# 06_IN_OUT.net
KiCad netlist of a schematic drawn in Altium Designer
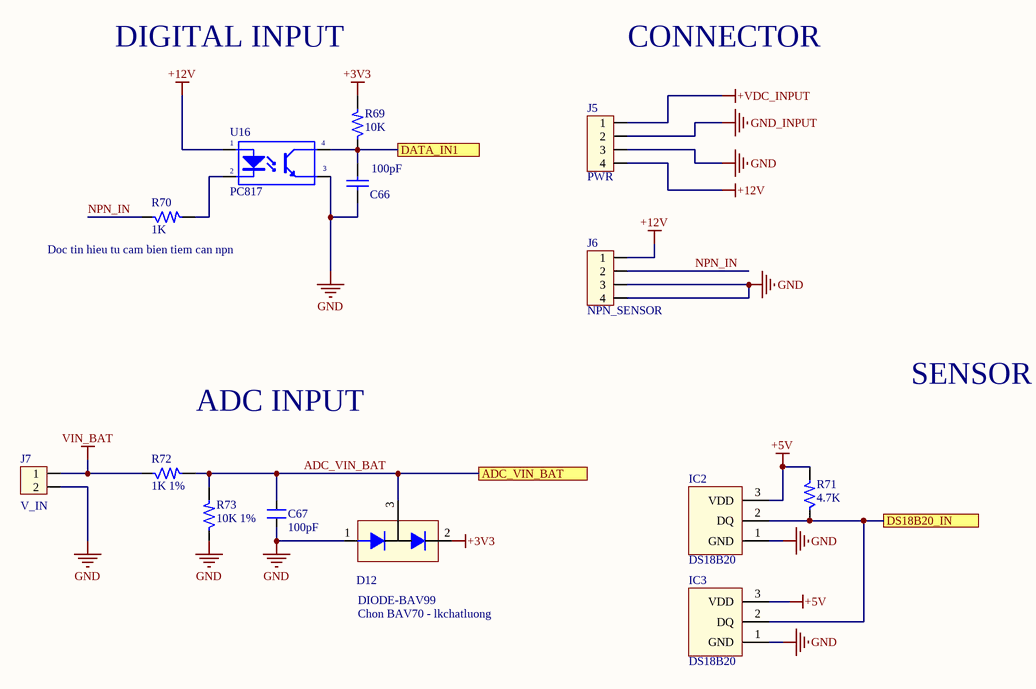
[diagram p0: [06]IN_OUT.SchDoc]

(export (version "E")
  (design (tool "Eeschema 10.0.6"))
  (components
    (comp (ref "C66")
      (value "100pF")
      (footprint "CAP_0805")
      (description "Capacitor")
      (fields (field (name "PUBLISHER") "Altium Limited"))
      (libsource (lib "My Library") (part "CapSMD"))
    )
    (comp (ref "C67")
      (value "100pF")
      (footprint "CAP_0805")
      (description "Cap SMD")
      (libsource (lib "khapham") (part "CM"))
    )
    (comp (ref "D12")
      (value "DIODE-BAV99")
      (footprint "SOT23")
      (description "ZENER, SOT23,")
      (fields
        (field (name "MANUFACTURER") "ON Semiconductor / Fairchild")
        (field (name "MANUFACTURER PART NUMBER") "BAV99")
        (field (name ".CREATOR") "LeKhaLinh")
        (field (name ".CHECKPCB") "LeKhaLinh")
        (field (name ".CHECKSCH") "LeKhaLinh")
      )
      (libsource (lib "GPS_Traking_V1_1") (part "DIODE-BAV99"))
    )
    (comp (ref "IC2")
      (value "DS18B20")
      (footprint "TO92")
      (description "High Precision  1-Wire® Digital Thermometer")
      (libsource (lib "My Library") (part "DS18S20"))
    )
    (comp (ref "IC3")
      (value "DS18B20")
      (footprint "TO92")
      (description "High Precision  1-Wire® Digital Thermometer")
      (libsource (lib "My Library") (part "DS18S20"))
    )
    (comp (ref "J5")
      (value "PWR")
      (footprint "Hed4V_3.96")
      (description "Header 4 (Green)")
      (libsource (lib "GPS_Traking_V1_1") (part "Hed4"))
    )
    (comp (ref "J6")
      (value "NPN_SENSOR")
      (footprint "CON_2.54mm_4")
      (description "Connector 4")
      (libsource (lib "GPS_Traking_V1_1") (part "Con4"))
    )
    (comp (ref "J7")
      (value "V_IN")
      (footprint "CON_2.54mm_2")
      (description "Connector 2")
      (libsource (lib "GPS_Traking_V1_1") (part "Con2"))
    )
    (comp (ref "R69")
      (value "10K")
      (footprint "RES-SMD-0805")
      (description "Resistor SMD")
      (libsource (lib "khapham") (part "RM"))
    )
    (comp (ref "R70")
      (value "1K")
      (footprint "RES-SMD-0805")
      (description "Resistor SMD")
      (libsource (lib "khapham") (part "RM"))
    )
    (comp (ref "R71")
      (value "4.7K")
      (footprint "RES-SMD-0805")
      (description "Resistor SMD")
      (libsource (lib "khapham") (part "RM"))
    )
    (comp (ref "R72")
      (value "1K 1%")
      (footprint "RES-SMD-0805")
      (description "Resistor SMD")
      (libsource (lib "khapham") (part "RM"))
    )
    (comp (ref "R73")
      (value "10K 1%")
      (footprint "RES-SMD-0805")
      (description "Resistor SMD")
      (libsource (lib "khapham") (part "RM"))
    )
    (comp (ref "U16")
      (value "PC817")
      (footprint "PC817x1SMD")
      (description "Single Opto")
      (libsource (lib "GPS_Traking_V1_1") (part "PC817"))
    )
  )
  (nets
    (net (code "1") (name "+3V3") (class "Default")
      (node (ref "D12") (pin "2") (pinfunction "2_2") (pintype "passive"))
      (node (ref "R69") (pin "2") (pinfunction "2_2") (pintype "passive"))
    )
    (net (code "2") (name "+5V") (class "Default")
      (node (ref "IC2") (pin "3") (pinfunction "VDD_3") (pintype "passive"))
      (node (ref "IC3") (pin "3") (pinfunction "VDD_3") (pintype "passive"))
      (node (ref "R71") (pin "2") (pinfunction "2_2") (pintype "passive"))
    )
    (net (code "3") (name "+12V") (class "Default")
      (node (ref "J5") (pin "4") (pinfunction "4_4") (pintype "passive"))
      (node (ref "J6") (pin "1") (pinfunction "1_1") (pintype "passive"))
      (node (ref "U16") (pin "1") (pinfunction "A_1") (pintype "passive"))
    )
    (net (code "4") (name "+VDC_INPUT") (class "Default")
      (node (ref "J5") (pin "1") (pinfunction "1_1") (pintype "passive"))
    )
    (net (code "5") (name "/ADC_VIN_BAT") (class "Default")
      (node (ref "C67") (pin "2") (pinfunction "2_2") (pintype "passive"))
      (node (ref "D12") (pin "3") (pinfunction "3_3") (pintype "passive"))
      (node (ref "R72") (pin "2") (pinfunction "2_2") (pintype "passive"))
      (node (ref "R73") (pin "2") (pinfunction "2_2") (pintype "passive"))
    )
    (net (code "6") (name "/DATA_IN1") (class "Default")
      (node (ref "C66") (pin "1") (pinfunction "1_1") (pintype "passive"))
      (node (ref "R69") (pin "1") (pinfunction "1_1") (pintype "passive"))
      (node (ref "U16") (pin "4") (pinfunction "C_4") (pintype "passive"))
    )
    (net (code "7") (name "/DS18B20_IN") (class "Default")
      (node (ref "IC2") (pin "2") (pinfunction "DQ_2") (pintype "passive"))
      (node (ref "IC3") (pin "2") (pinfunction "DQ_2") (pintype "passive"))
      (node (ref "R71") (pin "1") (pinfunction "1_1") (pintype "passive"))
    )
    (net (code "8") (name "/NPN_IN") (class "Default")
      (node (ref "J6") (pin "2") (pinfunction "2_2") (pintype "passive"))
      (node (ref "R70") (pin "1") (pinfunction "1_1") (pintype "passive"))
    )
    (net (code "9") (name "GND") (class "Default")
      (node (ref "C66") (pin "2") (pinfunction "2_2") (pintype "passive"))
      (node (ref "C67") (pin "1") (pinfunction "1_1") (pintype "passive"))
      (node (ref "D12") (pin "1") (pinfunction "1_1") (pintype "passive"))
      (node (ref "IC2") (pin "1") (pinfunction "GND_1") (pintype "passive"))
      (node (ref "IC3") (pin "1") (pinfunction "GND_1") (pintype "passive"))
      (node (ref "J5") (pin "3") (pinfunction "3_3") (pintype "passive"))
      (node (ref "J6") (pin "3") (pinfunction "3_3") (pintype "passive"))
      (node (ref "J6") (pin "4") (pinfunction "4_4") (pintype "passive"))
      (node (ref "J7") (pin "2") (pinfunction "2_2") (pintype "passive"))
      (node (ref "R73") (pin "1") (pinfunction "1_1") (pintype "passive"))
      (node (ref "U16") (pin "3") (pinfunction "E_3") (pintype "passive"))
    )
    (net (code "10") (name "GND_INPUT") (class "Default")
      (node (ref "J5") (pin "2") (pinfunction "2_2") (pintype "passive"))
    )
    (net (code "11") (name "Net-(U16-K)") (class "Default")
      (node (ref "R70") (pin "2") (pinfunction "2_2") (pintype "passive"))
      (node (ref "U16") (pin "2") (pinfunction "K_2") (pintype "passive"))
    )
    (net (code "12") (name "VIN_BAT") (class "Default")
      (node (ref "J7") (pin "1") (pinfunction "1_1") (pintype "passive"))
      (node (ref "R72") (pin "1") (pinfunction "1_1") (pintype "passive"))
    )
  )
)
